# BluetoothConnectivity.net
KiCad netlist of a schematic drawn in Altium Designer
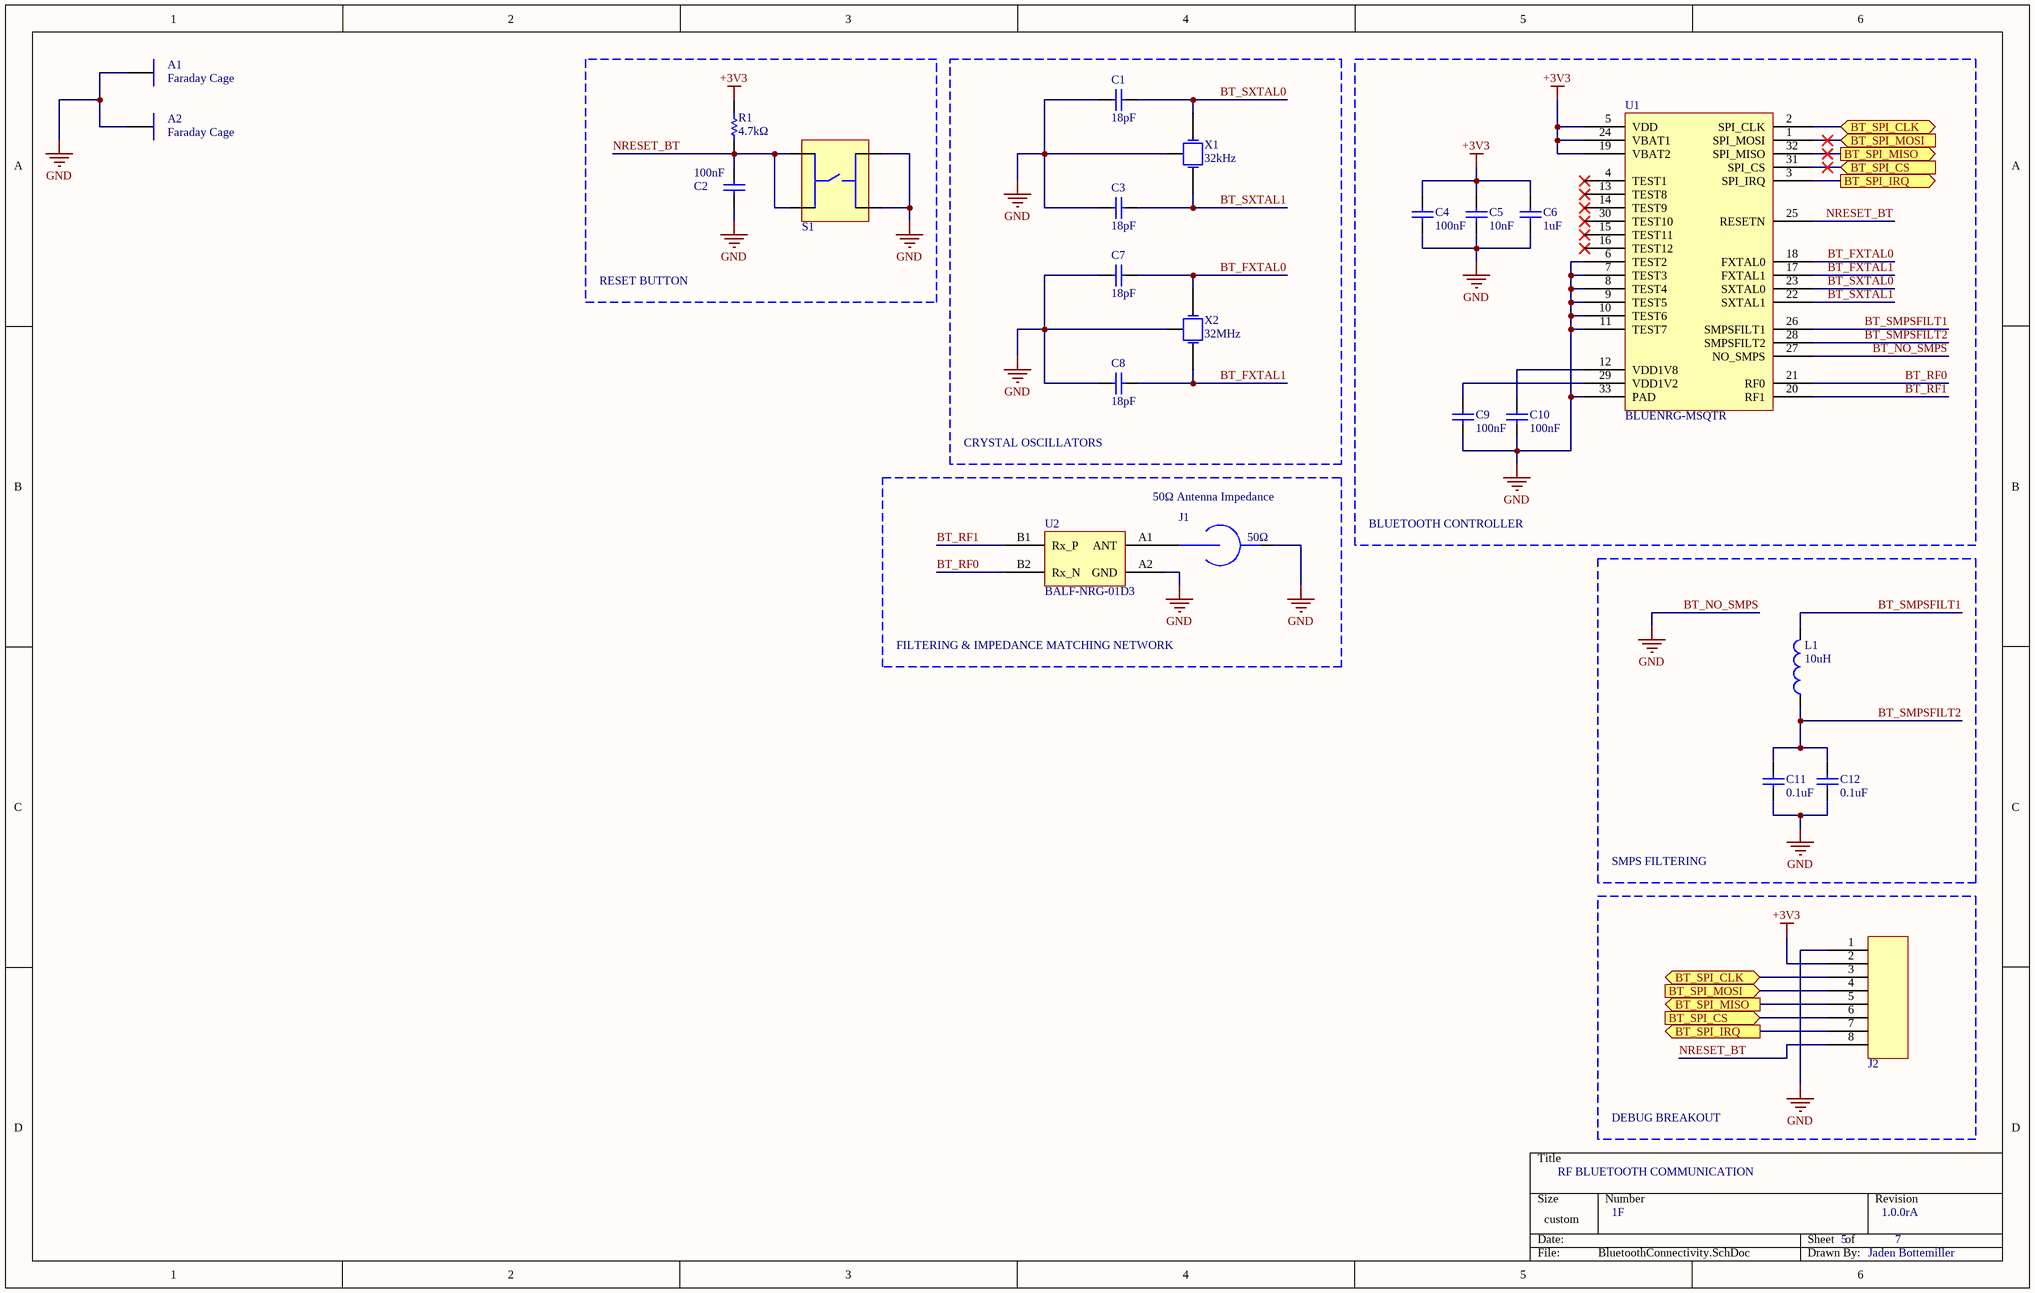
[diagram p0: BluetoothConnectivity.SchDoc]

(export (version "E")
  (design (tool "Eeschema 10.0.6"))
  (components
    (comp (ref "A1")
      (value "Faraday Cage")
      (description "Standard Faraday Cage")
      (libsource (lib "NikoboticsLib") (part "Faraday Cage"))
    )
    (comp (ref "A2")
      (value "Faraday Cage")
      (description "Standard Faraday Cage")
      (libsource (lib "NikoboticsLib") (part "Faraday Cage"))
    )
    (comp (ref "C1")
      (value "18pF")
      (description "Standard Capacitor")
      (fields (field (name "Comment") "CAP"))
      (libsource (lib "NikoboticsLib") (part "CAP"))
    )
    (comp (ref "C2")
      (value "100nF")
      (description "Standard Capacitor")
      (fields (field (name "Comment") "CAP"))
      (libsource (lib "NikoboticsLib") (part "CAP"))
    )
    (comp (ref "C3")
      (value "18pF")
      (description "Standard Capacitor")
      (fields (field (name "Comment") "CAP"))
      (libsource (lib "NikoboticsLib") (part "CAP"))
    )
    (comp (ref "C4")
      (value "100nF")
      (description "Standard Capacitor")
      (fields (field (name "Comment") "CAP"))
      (libsource (lib "NikoboticsLib") (part "CAP"))
    )
    (comp (ref "C5")
      (value "10nF")
      (description "Standard Capacitor")
      (fields (field (name "Comment") "CAP"))
      (libsource (lib "NikoboticsLib") (part "CAP"))
    )
    (comp (ref "C6")
      (value "1uF")
      (description "Standard Capacitor")
      (fields (field (name "Comment") "CAP"))
      (libsource (lib "NikoboticsLib") (part "CAP"))
    )
    (comp (ref "C7")
      (value "18pF")
      (description "Standard Capacitor")
      (fields (field (name "Comment") "CAP"))
      (libsource (lib "NikoboticsLib") (part "CAP"))
    )
    (comp (ref "C8")
      (value "18pF")
      (description "Standard Capacitor")
      (fields (field (name "Comment") "CAP"))
      (libsource (lib "NikoboticsLib") (part "CAP"))
    )
    (comp (ref "C9")
      (value "100nF")
      (description "Standard Capacitor")
      (fields (field (name "Comment") "CAP"))
      (libsource (lib "NikoboticsLib") (part "CAP"))
    )
    (comp (ref "C10")
      (value "100nF")
      (description "Standard Capacitor")
      (fields (field (name "Comment") "CAP"))
      (libsource (lib "NikoboticsLib") (part "CAP"))
    )
    (comp (ref "C11")
      (value "0.1uF")
      (description "Standard Capacitor")
      (fields (field (name "Comment") "CAP"))
      (libsource (lib "NikoboticsLib") (part "CAP"))
    )
    (comp (ref "C12")
      (value "0.1uF")
      (description "Standard Capacitor")
      (fields (field (name "Comment") "CAP"))
      (libsource (lib "NikoboticsLib") (part "CAP"))
    )
    (comp (ref "J1")
      (value "Coaxial Connection")
      (description "Coaxial Connection, e.g. to antennae")
      (fields (field (name "IMPEDANCE") "50Ω"))
      (libsource (lib "NikoboticsLib") (part "COAX"))
    )
    (comp (ref "J2")
      (value "8 Pin Connector")
      (description "Standard 8 Pin Connector")
      (libsource (lib "NikoboticsLib") (part "CONN_8PIN"))
    )
    (comp (ref "L1")
      (value "10uH")
      (description "Standard Inductor")
      (fields (field (name "Comment") "IND"))
      (libsource (lib "NikoboticsLib") (part "IND"))
    )
    (comp (ref "R1")
      (value "4.7kΩ")
      (description "Standard Resistor")
      (fields (field (name "TOLERANCE") "1%") (field (name "Comment") "RES"))
      (libsource (lib "NikoboticsLib") (part "RES"))
    )
    (comp (ref "S1")
      (value "Pushbutton")
      (description "Standard Pushbutton with 4 Terminals")
      (libsource (lib "NikoboticsLib") (part "PUSHBTN_4T"))
    )
    (comp (ref "U1")
      (value "BLUENRG-MSQTR")
      (description "IC RF TxRx + MCU Bluetooth Bluetooth v4.1 2.4GHz 32-VFQFN Exposed Pad")
      (libsource (lib "NikoboticsLib") (part "BLUENRG-MSQTR"))
    )
    (comp (ref "U2")
      (value "BALF-NRG-01D3")
      (description "RF Balun 2.4GHz ~ 2.5GHz 50 / 50Ohm 4-WFBGA, FCBGA")
      (libsource (lib "NikoboticsLib") (part "BALF-NRG-01D3"))
    )
    (comp (ref "X1")
      (value "32kHz")
      (description "Standard Crystal Oscillator with a ground connection.")
      (fields (field (name "Comment") "Crystal Oscillator"))
      (libsource (lib "NikoboticsLib") (part "OSC_1GND"))
    )
    (comp (ref "X2")
      (value "32MHz")
      (description "Standard Crystal Oscillator with a ground connection.")
      (fields (field (name "Comment") "Crystal Oscillator"))
      (libsource (lib "NikoboticsLib") (part "OSC_1GND"))
    )
  )
  (nets
    (net (code "1") (name "+3V3") (class "Default")
      (node (ref "C4") (pin "2") (pinfunction "2_2") (pintype "passive"))
      (node (ref "C5") (pin "2") (pinfunction "2_2") (pintype "passive"))
      (node (ref "C6") (pin "2") (pinfunction "2_2") (pintype "passive"))
      (node (ref "J2") (pin "2") (pinfunction "Pin_2") (pintype "passive"))
      (node (ref "R1") (pin "2") (pinfunction "2_2") (pintype "passive"))
      (node (ref "U1") (pin "19") (pinfunction "VBAT2_19") (pintype "passive"))
      (node (ref "U1") (pin "24") (pinfunction "VBAT1_24") (pintype "passive"))
      (node (ref "U1") (pin "5") (pinfunction "VDD_5") (pintype "passive"))
    )
    (net (code "2") (name "/BT_FXTAL0") (class "Default")
      (node (ref "C7") (pin "1") (pinfunction "1_1") (pintype "passive"))
      (node (ref "U1") (pin "18") (pinfunction "FXTAL0_18") (pintype "passive"))
      (node (ref "X2") (pin "1") (pinfunction "X1_1") (pintype "passive"))
    )
    (net (code "3") (name "/BT_FXTAL1") (class "Default")
      (node (ref "C8") (pin "1") (pinfunction "1_1") (pintype "passive"))
      (node (ref "U1") (pin "17") (pinfunction "FXTAL1_17") (pintype "passive"))
      (node (ref "X2") (pin "2") (pinfunction "X2_2") (pintype "passive"))
    )
    (net (code "4") (name "/BT_RF0") (class "Default")
      (node (ref "U1") (pin "21") (pinfunction "RF0_21") (pintype "passive"))
      (node (ref "U2") (pin "B2") (pinfunction "Rx_N_B2") (pintype "passive"))
    )
    (net (code "5") (name "/BT_RF1") (class "Default")
      (node (ref "U1") (pin "20") (pinfunction "RF1_20") (pintype "passive"))
      (node (ref "U2") (pin "B1") (pinfunction "Rx_P_B1") (pintype "passive"))
    )
    (net (code "6") (name "/BT_SMPSFILT1") (class "Default")
      (node (ref "L1") (pin "2") (pinfunction "2_2") (pintype "passive"))
      (node (ref "U1") (pin "26") (pinfunction "SMPSFILT1_26") (pintype "passive"))
    )
    (net (code "7") (name "/BT_SMPSFILT2") (class "Default")
      (node (ref "C11") (pin "2") (pinfunction "2_2") (pintype "passive"))
      (node (ref "C12") (pin "2") (pinfunction "2_2") (pintype "passive"))
      (node (ref "L1") (pin "1") (pinfunction "1_1") (pintype "passive"))
      (node (ref "U1") (pin "28") (pinfunction "SMPSFILT2_28") (pintype "passive"))
    )
    (net (code "8") (name "/BT_SPI_CLK") (class "Default")
      (node (ref "J2") (pin "3") (pinfunction "Pin_3") (pintype "passive"))
      (node (ref "U1") (pin "2") (pinfunction "SPI_CLK_2") (pintype "passive"))
    )
    (net (code "9") (name "/BT_SPI_CS") (class "Default")
      (node (ref "J2") (pin "6") (pinfunction "Pin_6") (pintype "passive"))
      (node (ref "U1") (pin "31") (pinfunction "SPI_CS_31") (pintype "passive"))
    )
    (net (code "10") (name "/BT_SPI_IRQ") (class "Default")
      (node (ref "J2") (pin "7") (pinfunction "Pin_7") (pintype "passive"))
      (node (ref "U1") (pin "3") (pinfunction "SPI_IRQ_3") (pintype "passive"))
    )
    (net (code "11") (name "/BT_SPI_MISO") (class "Default")
      (node (ref "J2") (pin "5") (pinfunction "Pin_5") (pintype "passive"))
      (node (ref "U1") (pin "32") (pinfunction "SPI_MISO_32") (pintype "passive"))
    )
    (net (code "12") (name "/BT_SPI_MOSI") (class "Default")
      (node (ref "J2") (pin "4") (pinfunction "Pin_4") (pintype "passive"))
      (node (ref "U1") (pin "1") (pinfunction "SPI_MOSI_1") (pintype "passive"))
    )
    (net (code "13") (name "/BT_SXTAL0") (class "Default")
      (node (ref "C1") (pin "1") (pinfunction "1_1") (pintype "passive"))
      (node (ref "U1") (pin "23") (pinfunction "SXTAL0_23") (pintype "passive"))
      (node (ref "X1") (pin "1") (pinfunction "X1_1") (pintype "passive"))
    )
    (net (code "14") (name "/BT_SXTAL1") (class "Default")
      (node (ref "C3") (pin "1") (pinfunction "1_1") (pintype "passive"))
      (node (ref "U1") (pin "22") (pinfunction "SXTAL1_22") (pintype "passive"))
      (node (ref "X1") (pin "2") (pinfunction "X2_2") (pintype "passive"))
    )
    (net (code "15") (name "/NRESET_BT") (class "Default")
      (node (ref "C2") (pin "2") (pinfunction "2_2") (pintype "passive"))
      (node (ref "J2") (pin "8") (pinfunction "Pin_8") (pintype "passive"))
      (node (ref "R1") (pin "1") (pinfunction "1_1") (pintype "passive"))
      (node (ref "S1") (pin "1") (pintype "passive"))
      (node (ref "S1") (pin "2") (pinfunction "Pin_2") (pintype "passive"))
      (node (ref "U1") (pin "25") (pinfunction "RESETN_25") (pintype "passive"))
    )
    (net (code "16") (name "GND") (class "Default")
      (node (ref "A1") (pin "1") (pinfunction "Pin_1") (pintype "passive"))
      (node (ref "A2") (pin "1") (pinfunction "Pin_1") (pintype "passive"))
      (node (ref "C1") (pin "2") (pinfunction "2_2") (pintype "passive"))
      (node (ref "C10") (pin "1") (pinfunction "1_1") (pintype "passive"))
      (node (ref "C11") (pin "1") (pinfunction "1_1") (pintype "passive"))
      (node (ref "C12") (pin "1") (pinfunction "1_1") (pintype "passive"))
      (node (ref "C2") (pin "1") (pinfunction "1_1") (pintype "passive"))
      (node (ref "C3") (pin "2") (pinfunction "2_2") (pintype "passive"))
      (node (ref "C4") (pin "1") (pinfunction "1_1") (pintype "passive"))
      (node (ref "C5") (pin "1") (pinfunction "1_1") (pintype "passive"))
      (node (ref "C6") (pin "1") (pinfunction "1_1") (pintype "passive"))
      (node (ref "C7") (pin "2") (pinfunction "2_2") (pintype "passive"))
      (node (ref "C8") (pin "2") (pinfunction "2_2") (pintype "passive"))
      (node (ref "C9") (pin "1") (pinfunction "1_1") (pintype "passive"))
      (node (ref "J1") (pin "2") (pinfunction "2_2") (pintype "passive"))
      (node (ref "J2") (pin "1") (pinfunction "Pin_1") (pintype "passive"))
      (node (ref "S1") (pin "3") (pinfunction "Pin_3") (pintype "passive"))
      (node (ref "S1") (pin "4") (pinfunction "Pin_4") (pintype "passive"))
      (node (ref "U1") (pin "10") (pinfunction "TEST6_10") (pintype "passive"))
      (node (ref "U1") (pin "11") (pinfunction "TEST7_11") (pintype "passive"))
      (node (ref "U1") (pin "27") (pinfunction "NO_SMPS_27") (pintype "passive"))
      (node (ref "U1") (pin "33") (pinfunction "PAD_33") (pintype "passive"))
      (node (ref "U1") (pin "6") (pinfunction "TEST2_6") (pintype "passive"))
      (node (ref "U1") (pin "7") (pinfunction "TEST3_7") (pintype "passive"))
      (node (ref "U1") (pin "8") (pinfunction "TEST4_8") (pintype "passive"))
      (node (ref "U1") (pin "9") (pinfunction "TEST5_9") (pintype "passive"))
      (node (ref "U2") (pin "A2") (pinfunction "GND_A2") (pintype "passive"))
      (node (ref "X1") (pin "3") (pinfunction "GND_3") (pintype "passive"))
      (node (ref "X2") (pin "3") (pinfunction "GND_3") (pintype "passive"))
    )
    (net (code "17") (name "Net-(J1-Pin)") (class "Default")
      (node (ref "J1") (pin "1") (pinfunction "Pin_1") (pintype "passive"))
      (node (ref "U2") (pin "A1") (pinfunction "ANT_A1") (pintype "passive"))
    )
    (net (code "18") (name "Net-(U1-VDD1V2)") (class "Default")
      (node (ref "C9") (pin "2") (pinfunction "2_2") (pintype "passive"))
      (node (ref "U1") (pin "29") (pinfunction "VDD1V2_29") (pintype "passive"))
    )
    (net (code "19") (name "Net-(U1-VDD1V8)") (class "Default")
      (node (ref "C10") (pin "2") (pinfunction "2_2") (pintype "passive"))
      (node (ref "U1") (pin "12") (pinfunction "VDD1V8_12") (pintype "passive"))
    )
    (net (code "20") (name "unconnected-(U1-TEST1-Pad4)") (class "Default")
      (node (ref "U1") (pin "4") (pinfunction "TEST1_4") (pintype "passive+no_connect"))
    )
    (net (code "21") (name "unconnected-(U1-TEST8-Pad13)") (class "Default")
      (node (ref "U1") (pin "13") (pinfunction "TEST8_13") (pintype "passive+no_connect"))
    )
    (net (code "22") (name "unconnected-(U1-TEST9-Pad14)") (class "Default")
      (node (ref "U1") (pin "14") (pinfunction "TEST9_14") (pintype "passive+no_connect"))
    )
    (net (code "23") (name "unconnected-(U1-TEST10-Pad30)") (class "Default")
      (node (ref "U1") (pin "30") (pinfunction "TEST10_30") (pintype "passive+no_connect"))
    )
    (net (code "24") (name "unconnected-(U1-TEST11-Pad15)") (class "Default")
      (node (ref "U1") (pin "15") (pinfunction "TEST11_15") (pintype "passive+no_connect"))
    )
    (net (code "25") (name "unconnected-(U1-TEST12-Pad16)") (class "Default")
      (node (ref "U1") (pin "16") (pinfunction "TEST12_16") (pintype "passive+no_connect"))
    )
  )
)
